# ColdBlock_PID_LCD00.net
KiCad netlist of a schematic drawn in Altium Designer
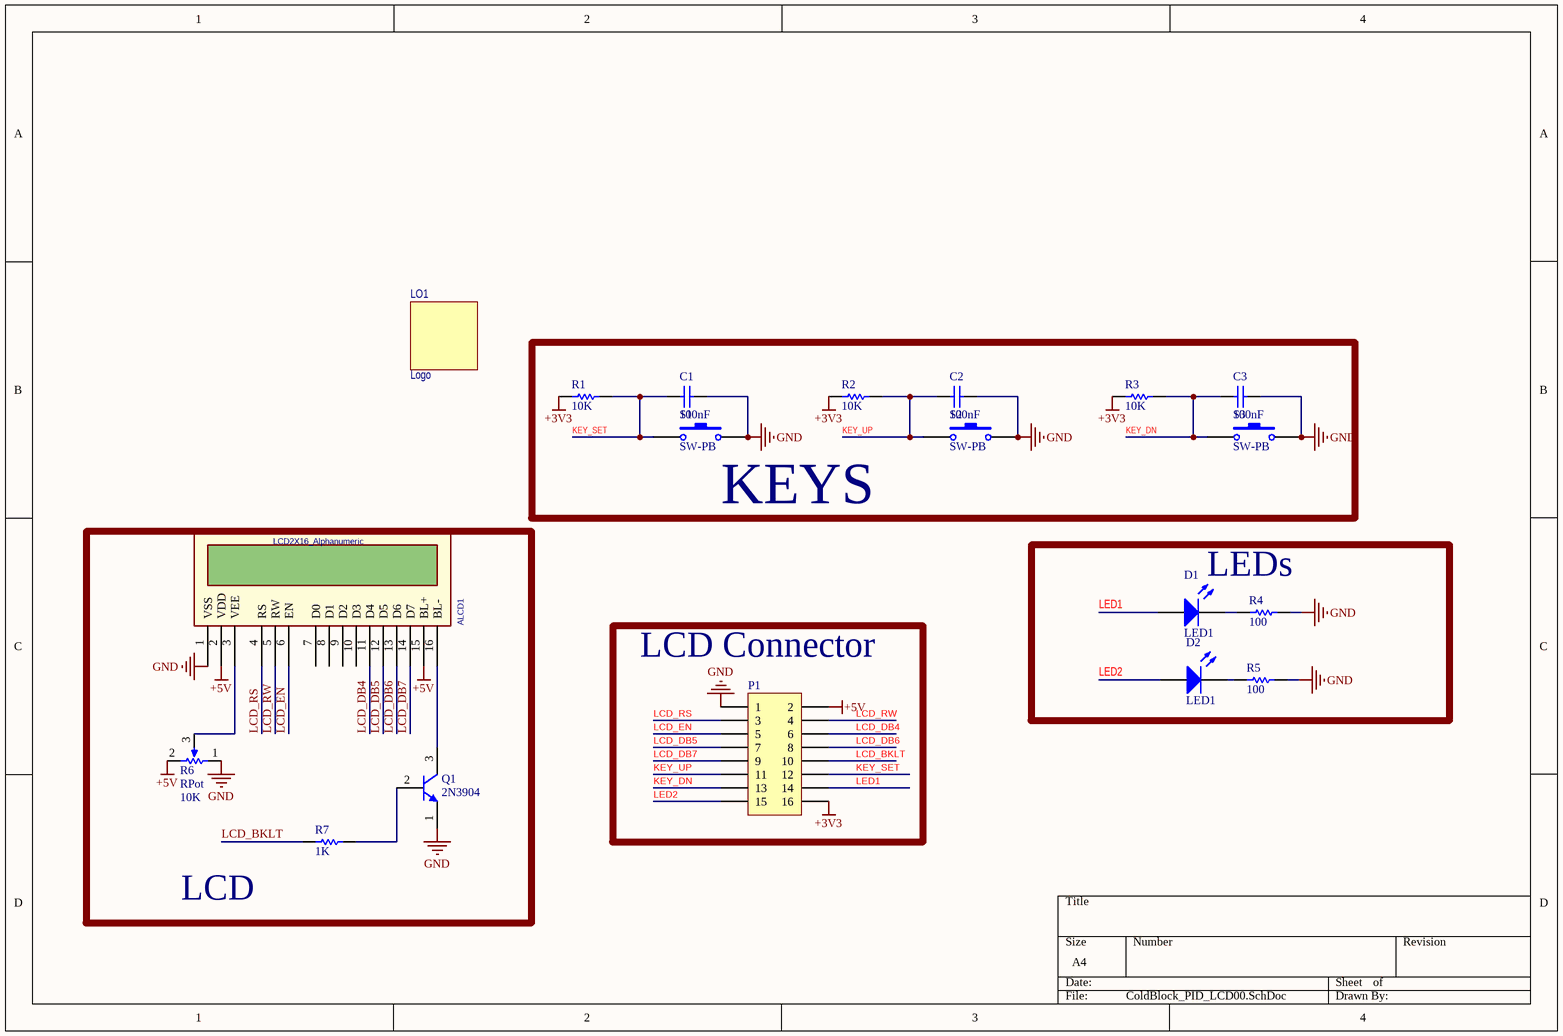
[diagram p0: ColdBlock_PID_LCD00.SchDoc]

(export (version "E")
  (design (tool "Eeschema 10.0.6"))
  (components
    (comp (ref "ALCD1")
      (value "LCD2X16_Alphanumeric")
      (footprint "LCD_2X16 GREEN - 2.5mm")
      (fields (field (name "DESIGNER") "Abbas Basereh"))
      (libsource (lib "Mofidi3D") (part "LCD2X16_Alphanumeric"))
    )
    (comp (ref "C1")
      (value "100nF")
      (footprint "CAP_MLCC_RAD_0.1")
      (description "Capacitor")
      (fields (field (name "Comment") "Cap") (field (name "PUBLISHER") "Altium Limited"))
      (libsource (lib "Miscellaneous Devices") (part "Cap"))
    )
    (comp (ref "C2")
      (value "100nF")
      (footprint "CAP_MLCC_RAD_0.1")
      (description "Capacitor")
      (fields (field (name "Comment") "Cap") (field (name "PUBLISHER") "Altium Limited"))
      (libsource (lib "Miscellaneous Devices") (part "Cap"))
    )
    (comp (ref "C3")
      (value "100nF")
      (footprint "CAP_MLCC_RAD_0.1")
      (description "Capacitor")
      (fields (field (name "Comment") "Cap") (field (name "PUBLISHER") "Altium Limited"))
      (libsource (lib "Miscellaneous Devices") (part "Cap"))
    )
    (comp (ref "D1")
      (value "LED1")
      (footprint "LED5MM_BLUE")
      (description "Typical RED GaAs LED")
      (fields (field (name "PUBLISHER") "Altium Limited"))
      (libsource (lib "Miscellaneous Devices") (part "LED1"))
    )
    (comp (ref "D2")
      (value "LED1")
      (footprint "LED5MM_BLUE")
      (description "Typical RED GaAs LED")
      (fields (field (name "PUBLISHER") "Altium Limited"))
      (libsource (lib "Miscellaneous Devices") (part "LED1"))
    )
    (comp (ref "LO1") (value "Logo") (footprint "LOGO_PARS_TOP") (libsource (lib "Mofidi3D") (part "Logo")))
    (comp (ref "P1")
      (value "Header 8X2")
      (footprint "IDC2.54_16PIN")
      (description "Header, 8-Pin, Dual row")
      (fields (field (name "PUBLISHER") "Altium Limited"))
      (libsource (lib "Miscellaneous Connectors") (part "Header 8X2"))
    )
    (comp (ref "Q1")
      (value "2N3904")
      (footprint "TO-92 STR")
      (description "NPN General Purpose Amplifier")
      (fields (field (name "PUBLISHER") "Altium Limited"))
      (libsource (lib "Miscellaneous Devices") (part "2N3904"))
    )
    (comp (ref "R1")
      (value "10K")
      (footprint "Axial 0_25 W, 0_4 IN LEAD PITCH")
      (description "Resistor")
      (fields (field (name "Comment") "Res1") (field (name "PUBLISHER") "Altium Limited"))
      (libsource (lib "Miscellaneous Devices") (part "Res1"))
    )
    (comp (ref "R2")
      (value "10K")
      (footprint "Axial 0_25 W, 0_4 IN LEAD PITCH")
      (description "Resistor")
      (fields (field (name "Comment") "Res1") (field (name "PUBLISHER") "Altium Limited"))
      (libsource (lib "Miscellaneous Devices") (part "Res1"))
    )
    (comp (ref "R3")
      (value "10K")
      (footprint "Axial 0_25 W, 0_4 IN LEAD PITCH")
      (description "Resistor")
      (fields (field (name "Comment") "Res1") (field (name "PUBLISHER") "Altium Limited"))
      (libsource (lib "Miscellaneous Devices") (part "Res1"))
    )
    (comp (ref "R4")
      (value "100")
      (footprint "Axial 0_25 W, 0_4 IN LEAD PITCH")
      (description "Resistor")
      (fields (field (name "Comment") "Res1") (field (name "PUBLISHER") "Altium Limited"))
      (libsource (lib "Miscellaneous Devices") (part "Res1"))
    )
    (comp (ref "R5")
      (value "100")
      (footprint "Axial 0_25 W, 0_4 IN LEAD PITCH")
      (description "Resistor")
      (fields (field (name "Comment") "Res1") (field (name "PUBLISHER") "Altium Limited"))
      (libsource (lib "Miscellaneous Devices") (part "Res1"))
    )
    (comp (ref "R6")
      (value "RPot")
      (footprint "Potentiometer_EVND8")
      (description "Potentiometer")
      (fields (field (name "ALTIUM_VALUE") "10K") (field (name "PUBLISHER") "Altium Limited"))
      (libsource (lib "Miscellaneous Devices") (part "RPot"))
    )
    (comp (ref "R7")
      (value "1K")
      (footprint "Axial 0_25 W, 0_4 IN LEAD PITCH")
      (description "Resistor")
      (fields (field (name "Comment") "Res1") (field (name "PUBLISHER") "Altium Limited"))
      (libsource (lib "Miscellaneous Devices") (part "Res1"))
    )
    (comp (ref "S1")
      (value "SW-PB")
      (footprint "SW-4PIN")
      (description "Switch")
      (fields (field (name "PUBLISHER") "Altium Limited"))
      (libsource (lib "Miscellaneous Devices") (part "SW-PB"))
    )
    (comp (ref "S2")
      (value "SW-PB")
      (footprint "SW-4PIN")
      (description "Switch")
      (fields (field (name "PUBLISHER") "Altium Limited"))
      (libsource (lib "Miscellaneous Devices") (part "SW-PB"))
    )
    (comp (ref "S3")
      (value "SW-PB")
      (footprint "SW-4PIN")
      (description "Switch")
      (fields (field (name "PUBLISHER") "Altium Limited"))
      (libsource (lib "Miscellaneous Devices") (part "SW-PB"))
    )
  )
  (nets
    (net (code "1") (name "+3V3") (class "Default")
      (node (ref "P1") (pin "16") (pinfunction "16_16") (pintype "passive"))
      (node (ref "R1") (pin "2") (pinfunction "2_2") (pintype "passive"))
      (node (ref "R2") (pin "2") (pinfunction "2_2") (pintype "passive"))
      (node (ref "R3") (pin "2") (pinfunction "2_2") (pintype "passive"))
    )
    (net (code "2") (name "+5V") (class "Default")
      (node (ref "ALCD1") (pin "15") (pinfunction "BL+_15") (pintype "passive"))
      (node (ref "ALCD1") (pin "2") (pinfunction "VDD_2") (pintype "passive"))
      (node (ref "P1") (pin "2") (pinfunction "2_2") (pintype "passive"))
      (node (ref "R6") (pin "2") (pinfunction "BOT_2") (pintype "passive"))
    )
    (net (code "3") (name "/KEY_DN") (class "Default")
      (node (ref "C3") (pin "1") (pinfunction "1_1") (pintype "passive"))
      (node (ref "P1") (pin "13") (pinfunction "13_13") (pintype "passive"))
      (node (ref "R3") (pin "1") (pinfunction "1_1") (pintype "passive"))
      (node (ref "S3") (pin "1") (pinfunction "1_1") (pintype "passive"))
    )
    (net (code "4") (name "/KEY_SET") (class "Default")
      (node (ref "C1") (pin "1") (pinfunction "1_1") (pintype "passive"))
      (node (ref "P1") (pin "12") (pinfunction "12_12") (pintype "passive"))
      (node (ref "R1") (pin "1") (pinfunction "1_1") (pintype "passive"))
      (node (ref "S1") (pin "1") (pinfunction "1_1") (pintype "passive"))
    )
    (net (code "5") (name "/KEY_UP") (class "Default")
      (node (ref "C2") (pin "1") (pinfunction "1_1") (pintype "passive"))
      (node (ref "P1") (pin "11") (pinfunction "11_11") (pintype "passive"))
      (node (ref "R2") (pin "1") (pinfunction "1_1") (pintype "passive"))
      (node (ref "S2") (pin "1") (pinfunction "1_1") (pintype "passive"))
    )
    (net (code "6") (name "/LCD_BKLT") (class "Default")
      (node (ref "P1") (pin "10") (pinfunction "10_10") (pintype "passive"))
      (node (ref "R7") (pin "2") (pinfunction "2_2") (pintype "passive"))
    )
    (net (code "7") (name "/LCD_DB4") (class "Default")
      (node (ref "ALCD1") (pin "11") (pinfunction "D4_11") (pintype "passive"))
      (node (ref "P1") (pin "6") (pinfunction "6_6") (pintype "passive"))
    )
    (net (code "8") (name "/LCD_DB5") (class "Default")
      (node (ref "ALCD1") (pin "12") (pinfunction "D5_12") (pintype "passive"))
      (node (ref "P1") (pin "7") (pinfunction "7_7") (pintype "passive"))
    )
    (net (code "9") (name "/LCD_DB6") (class "Default")
      (node (ref "ALCD1") (pin "13") (pinfunction "D6_13") (pintype "passive"))
      (node (ref "P1") (pin "8") (pinfunction "8_8") (pintype "passive"))
    )
    (net (code "10") (name "/LCD_DB7") (class "Default")
      (node (ref "ALCD1") (pin "14") (pinfunction "D7_14") (pintype "passive"))
      (node (ref "P1") (pin "9") (pinfunction "9_9") (pintype "passive"))
    )
    (net (code "11") (name "/LCD_EN") (class "Default")
      (node (ref "ALCD1") (pin "6") (pinfunction "EN_6") (pintype "passive"))
      (node (ref "P1") (pin "5") (pinfunction "5_5") (pintype "passive"))
    )
    (net (code "12") (name "/LCD_RS") (class "Default")
      (node (ref "ALCD1") (pin "4") (pinfunction "RS_4") (pintype "passive"))
      (node (ref "P1") (pin "3") (pinfunction "3_3") (pintype "passive"))
    )
    (net (code "13") (name "/LCD_RW") (class "Default")
      (node (ref "ALCD1") (pin "5") (pinfunction "RW_5") (pintype "passive"))
      (node (ref "P1") (pin "4") (pinfunction "4_4") (pintype "passive"))
    )
    (net (code "14") (name "/LED1") (class "Default")
      (node (ref "D1") (pin "1") (pinfunction "A_1") (pintype "passive"))
      (node (ref "P1") (pin "14") (pinfunction "14_14") (pintype "passive"))
    )
    (net (code "15") (name "/LED2") (class "Default")
      (node (ref "D2") (pin "1") (pinfunction "A_1") (pintype "passive"))
      (node (ref "P1") (pin "15") (pinfunction "15_15") (pintype "passive"))
    )
    (net (code "16") (name "GND") (class "Default")
      (node (ref "ALCD1") (pin "1") (pinfunction "VSS_1") (pintype "passive"))
      (node (ref "C1") (pin "2") (pinfunction "2_2") (pintype "passive"))
      (node (ref "C2") (pin "2") (pinfunction "2_2") (pintype "passive"))
      (node (ref "C3") (pin "2") (pinfunction "2_2") (pintype "passive"))
      (node (ref "P1") (pin "1") (pinfunction "1_1") (pintype "passive"))
      (node (ref "Q1") (pin "1") (pinfunction "E_1") (pintype "passive"))
      (node (ref "R4") (pin "1") (pinfunction "1_1") (pintype "passive"))
      (node (ref "R5") (pin "1") (pinfunction "1_1") (pintype "passive"))
      (node (ref "R6") (pin "1") (pinfunction "TOP_1") (pintype "passive"))
      (node (ref "S1") (pin "2") (pinfunction "2_2") (pintype "passive"))
      (node (ref "S2") (pin "2") (pinfunction "2_2") (pintype "passive"))
      (node (ref "S3") (pin "2") (pinfunction "2_2") (pintype "passive"))
    )
    (net (code "17") (name "Net-(ALCD1-BL-)") (class "Default")
      (node (ref "ALCD1") (pin "16") (pinfunction "BL-_16") (pintype "passive"))
      (node (ref "Q1") (pin "3") (pinfunction "C_3") (pintype "passive"))
    )
    (net (code "18") (name "Net-(ALCD1-VEE)") (class "Default")
      (node (ref "ALCD1") (pin "3") (pinfunction "VEE_3") (pintype "passive"))
      (node (ref "R6") (pin "3") (pinfunction "TAP_3") (pintype "passive"))
    )
    (net (code "19") (name "Net-(D1-K)") (class "Default")
      (node (ref "D1") (pin "2") (pinfunction "K_2") (pintype "passive"))
      (node (ref "R4") (pin "2") (pinfunction "2_2") (pintype "passive"))
    )
    (net (code "20") (name "Net-(D2-K)") (class "Default")
      (node (ref "D2") (pin "2") (pinfunction "K_2") (pintype "passive"))
      (node (ref "R5") (pin "2") (pinfunction "2_2") (pintype "passive"))
    )
    (net (code "21") (name "Net-(Q1-B)") (class "Default")
      (node (ref "Q1") (pin "2") (pinfunction "B_2") (pintype "passive"))
      (node (ref "R7") (pin "1") (pinfunction "1_1") (pintype "passive"))
    )
    (net (code "22") (name "unconnected-(ALCD1-D0-Pad7)") (class "Default")
      (node (ref "ALCD1") (pin "7") (pinfunction "D0_7") (pintype "passive"))
    )
    (net (code "23") (name "unconnected-(ALCD1-D1-Pad8)") (class "Default")
      (node (ref "ALCD1") (pin "8") (pinfunction "D1_8") (pintype "passive"))
    )
    (net (code "24") (name "unconnected-(ALCD1-D2-Pad9)") (class "Default")
      (node (ref "ALCD1") (pin "9") (pinfunction "D2_9") (pintype "passive"))
    )
    (net (code "25") (name "unconnected-(ALCD1-D3-Pad10)") (class "Default")
      (node (ref "ALCD1") (pin "10") (pinfunction "D3_10") (pintype "passive"))
    )
  )
)
